# heater_control.net
KiCad netlist of a schematic drawn in Altium Designer
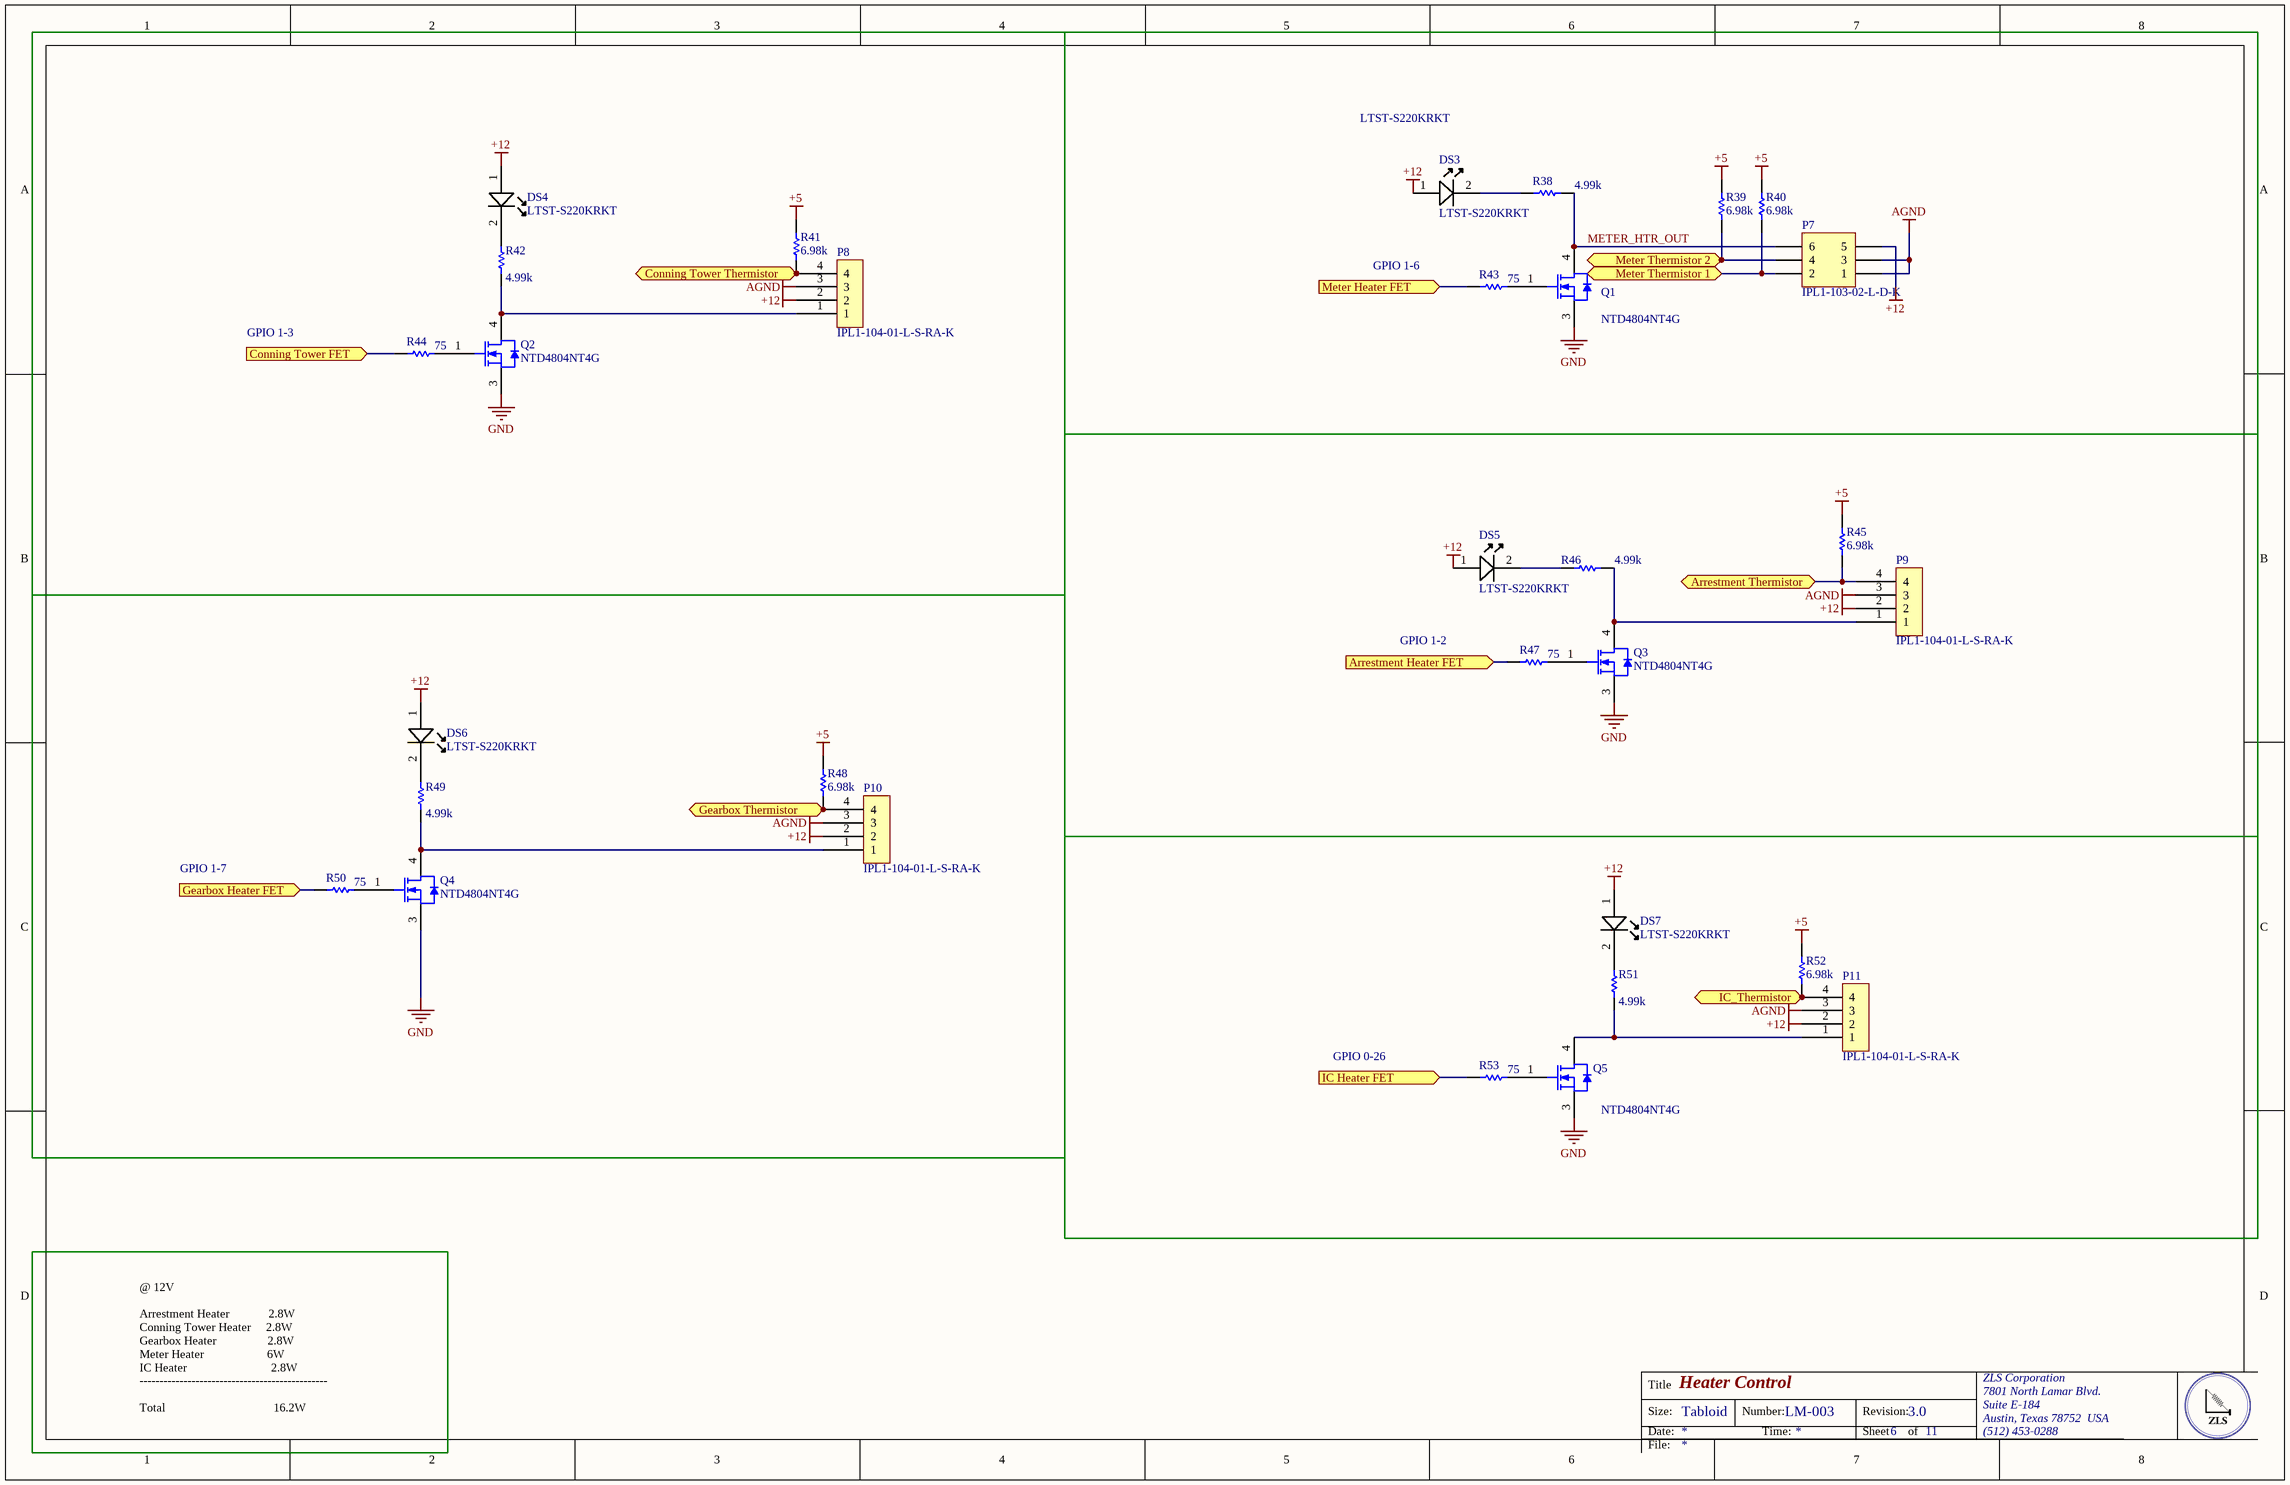
[diagram p0: heater_control.SchDoc]

(export (version "E")
  (design (tool "Eeschema 10.0.6"))
  (components
    (comp (ref "DS3")
      (value "Visible Name Value Type    False Description Lite-On LTST-S220KRKT Red LED, 631 nm 2012 (0805) Side View, Rectangle Lens SMD package STRING")
      (footprint "0805C_L")
      (fields
        (field (name "MANUFACTURER") "Vishay / Lite-On")
        (field (name "MANUFACTURER PART NUMBER") "LTST-S220KRKT")
      )
      (libsource (lib "*") (part "LED A/K"))
    )
    (comp (ref "DS4")
      (value "Visible Name Value Type    False Description Lite-On LTST-S220KRKT Red LED, 631 nm 2012 (0805) Side View, Rectangle Lens SMD package STRING")
      (footprint "0805C_L")
      (fields
        (field (name "MANUFACTURER") "Vishay / Lite-On")
        (field (name "MANUFACTURER PART NUMBER") "LTST-S220KRKT")
      )
      (libsource (lib "*") (part "LED A/K"))
    )
    (comp (ref "DS5")
      (value "Visible Name Value Type    False Description Lite-On LTST-S220KRKT Red LED, 631 nm 2012 (0805) Side View, Rectangle Lens SMD package STRING")
      (footprint "0805C_L")
      (fields
        (field (name "MANUFACTURER") "Vishay / Lite-On")
        (field (name "MANUFACTURER PART NUMBER") "LTST-S220KRKT")
      )
      (libsource (lib "*") (part "LED A/K"))
    )
    (comp (ref "DS6")
      (value "Visible Name Value Type    False Description Lite-On LTST-S220KRKT Red LED, 631 nm 2012 (0805) Side View, Rectangle Lens SMD package STRING")
      (footprint "0805C_L")
      (fields
        (field (name "MANUFACTURER") "Vishay / Lite-On")
        (field (name "MANUFACTURER PART NUMBER") "LTST-S220KRKT")
      )
      (libsource (lib "*") (part "LED A/K"))
    )
    (comp (ref "DS7")
      (value "Visible Name Value Type    False Description Lite-On LTST-S220KRKT Red LED, 631 nm 2012 (0805) Side View, Rectangle Lens SMD package STRING")
      (footprint "0805C_L")
      (fields
        (field (name "MANUFACTURER") "Vishay / Lite-On")
        (field (name "MANUFACTURER PART NUMBER") "LTST-S220KRKT")
      )
      (libsource (lib "*") (part "LED A/K"))
    )
    (comp (ref "P7")
      (value "IPL1-103-02-L-D-K")
      (footprint "IPL1-103-01-D")
      (description "CONN SHROUDED PWR HEADER 3POS")
      (libsource (lib "Miscellaneous Connectors") (part "Header 3X2H"))
    )
    (comp (ref "P8")
      (value "IPL1-104-01-L-S-RA-K")
      (footprint "IPL1-104-01")
      (description ".100 TERMINAL ASSY")
      (libsource (lib "ZLS_LIB") (part "53047-0410"))
    )
    (comp (ref "P9")
      (value "IPL1-104-01-L-S-RA-K")
      (footprint "IPL1-104-01")
      (description ".100 TERMINAL ASSY")
      (libsource (lib "ZLS_LIB") (part "53047-0410"))
    )
    (comp (ref "P10")
      (value "IPL1-104-01-L-S-RA-K")
      (footprint "IPL1-104-01")
      (description ".100 TERMINAL ASSY")
      (libsource (lib "ZLS_LIB") (part "53047-0410"))
    )
    (comp (ref "P11")
      (value "IPL1-104-01-L-S-RA-K")
      (footprint "IPL1-104-01")
      (description ".100 TERMINAL ASSY")
      (libsource (lib "ZLS_LIB") (part "53047-0410"))
    )
    (comp (ref "Q1")
      (value "NTD4804NT4G")
      (footprint "ONSC-DPAK-3-369AA-01_V")
      (description "Power MOSFET, 30 V, 117 A, Single N-Channel, 3-Pin DPAK, Pb-Free, Tape and Reel")
      (fields (field (name "MANUFACTURER") "On Semiconductor"))
      (libsource (lib "Altium Content Vault") (part "CMP-1058-00341-1"))
    )
    (comp (ref "Q2")
      (value "NTD4804NT4G")
      (footprint "ONSC-DPAK-3-369AA-01_V")
      (description "Power MOSFET, 30 V, 117 A, Single N-Channel, 3-Pin DPAK, Pb-Free, Tape and Reel")
      (fields (field (name "MANUFACTURER") "On Semiconductor"))
      (libsource (lib "Altium Content Vault") (part "CMP-1058-00341-1"))
    )
    (comp (ref "Q3")
      (value "NTD4804NT4G")
      (footprint "ONSC-DPAK-3-369AA-01_V")
      (description "Power MOSFET, 30 V, 117 A, Single N-Channel, 3-Pin DPAK, Pb-Free, Tape and Reel")
      (fields (field (name "MANUFACTURER") "On Semiconductor"))
      (libsource (lib "Altium Content Vault") (part "CMP-1058-00341-1"))
    )
    (comp (ref "Q4")
      (value "NTD4804NT4G")
      (footprint "ONSC-DPAK-3-369AA-01_V")
      (description "Power MOSFET, 30 V, 117 A, Single N-Channel, 3-Pin DPAK, Pb-Free, Tape and Reel")
      (fields (field (name "MANUFACTURER") "On Semiconductor"))
      (libsource (lib "Altium Content Vault") (part "CMP-1058-00341-1"))
    )
    (comp (ref "Q5")
      (value "NTD4804NT4G")
      (footprint "ONSC-DPAK-3-369AA-01_V")
      (description "Power MOSFET, 30 V, 117 A, Single N-Channel, 3-Pin DPAK, Pb-Free, Tape and Reel")
      (fields (field (name "MANUFACTURER") "On Semiconductor"))
      (libsource (lib "Altium Content Vault") (part "CMP-1058-00341-1"))
    )
    (comp (ref "R38")
      (value "~")
      (footprint "RESC0805(2012)_L")
      (fields
        (field (name "MANUFACTURER") "Vishay Dale")
        (field (name "MANUFACTURER PART NUMBER") "CRCW08054K99FKEA")
        (field (name "RESISTANCE (OHMS)") "4.99k")
        (field (name "TOLERANCE") "±1%")
      )
      (libsource (lib "Altium Content Vault") (part "CMP-1013-00393-1"))
    )
    (comp (ref "R39")
      (value "6K98 1% 0805(2012)")
      (footprint "RESC0805(2012)_N")
      (description "6K98 0.125W 1% 0805 (2012 Metric)  SMD")
      (fields
        (field (name "MANUFACTURER") "Vishay Dale")
        (field (name "MANUFACTURER PART NUMBER") "CRCW08056K98FKEA")
        (field (name "RESISTANCE (OHMS)") "6.98k")
      )
      (libsource (lib "Altium Content Vault") (part "CMP-1013-00606-1"))
    )
    (comp (ref "R40")
      (value "6K98 1% 0805(2012)")
      (footprint "RESC0805(2012)_N")
      (description "6K98 0.125W 1% 0805 (2012 Metric)  SMD")
      (fields
        (field (name "MANUFACTURER") "Vishay Dale")
        (field (name "MANUFACTURER PART NUMBER") "CRCW08056K98FKEA")
        (field (name "RESISTANCE (OHMS)") "6.98k")
      )
      (libsource (lib "Altium Content Vault") (part "CMP-1013-00606-1"))
    )
    (comp (ref "R41")
      (value "6K98 1% 0805(2012)")
      (footprint "RESC0805(2012)_N")
      (description "6K98 0.125W 1% 0805 (2012 Metric)  SMD")
      (fields
        (field (name "MANUFACTURER") "Vishay Dale")
        (field (name "MANUFACTURER PART NUMBER") "CRCW08056K98FKEA")
        (field (name "RESISTANCE (OHMS)") "6.98k")
      )
      (libsource (lib "Altium Content Vault") (part "CMP-1013-00606-1"))
    )
    (comp (ref "R42")
      (value "~")
      (footprint "RESC0805(2012)_L")
      (fields
        (field (name "MANUFACTURER") "Vishay Dale")
        (field (name "MANUFACTURER PART NUMBER") "CRCW08054K99FKEA")
        (field (name "RESISTANCE (OHMS)") "4.99k")
        (field (name "TOLERANCE") "±1%")
      )
      (libsource (lib "Altium Content Vault") (part "CMP-1013-00393-1"))
    )
    (comp (ref "R43")
      (value "~")
      (footprint "RESC0805(2012)_L")
      (fields
        (field (name "MANUFACTURER") "Vishay Dale")
        (field (name "MANUFACTURER PART NUMBER") "CRCW080575R0FKEA")
        (field (name "RESISTANCE (OHMS)") "75")
        (field (name "TOLERANCE") "±1%")
      )
      (libsource (lib "Altium Content Vault") (part "CMP-1013-00393-1"))
    )
    (comp (ref "R44")
      (value "~")
      (footprint "RESC0805(2012)_L")
      (fields
        (field (name "MANUFACTURER") "Vishay Dale")
        (field (name "MANUFACTURER PART NUMBER") "CRCW080575R0FKEA")
        (field (name "RESISTANCE (OHMS)") "75")
        (field (name "TOLERANCE") "±1%")
      )
      (libsource (lib "Altium Content Vault") (part "CMP-1013-00393-1"))
    )
    (comp (ref "R45")
      (value "6K98 1% 0805(2012)")
      (footprint "RESC0805(2012)_N")
      (description "6K98 0.125W 1% 0805 (2012 Metric)  SMD")
      (fields
        (field (name "MANUFACTURER") "Vishay Dale")
        (field (name "MANUFACTURER PART NUMBER") "CRCW08056K98FKEA")
        (field (name "RESISTANCE (OHMS)") "6.98k")
      )
      (libsource (lib "Altium Content Vault") (part "CMP-1013-00606-1"))
    )
    (comp (ref "R46")
      (value "~")
      (footprint "RESC0805(2012)_L")
      (fields
        (field (name "MANUFACTURER") "Vishay Dale")
        (field (name "MANUFACTURER PART NUMBER") "CRCW08054K99FKEA")
        (field (name "RESISTANCE (OHMS)") "4.99k")
        (field (name "TOLERANCE") "±1%")
      )
      (libsource (lib "Altium Content Vault") (part "CMP-1013-00393-1"))
    )
    (comp (ref "R47")
      (value "~")
      (footprint "RESC0805(2012)_L")
      (fields
        (field (name "MANUFACTURER") "Vishay Dale")
        (field (name "MANUFACTURER PART NUMBER") "CRCW080575R0FKEA")
        (field (name "RESISTANCE (OHMS)") "75")
        (field (name "TOLERANCE") "±1%")
      )
      (libsource (lib "Altium Content Vault") (part "CMP-1013-00393-1"))
    )
    (comp (ref "R48")
      (value "6K98 1% 0805(2012)")
      (footprint "RESC0805(2012)_N")
      (description "6K98 0.125W 1% 0805 (2012 Metric)  SMD")
      (fields
        (field (name "MANUFACTURER") "Vishay Dale")
        (field (name "MANUFACTURER PART NUMBER") "CRCW08056K98FKEA")
        (field (name "RESISTANCE (OHMS)") "6.98k")
      )
      (libsource (lib "Altium Content Vault") (part "CMP-1013-00606-1"))
    )
    (comp (ref "R49")
      (value "~")
      (footprint "RESC0805(2012)_L")
      (fields
        (field (name "MANUFACTURER") "Vishay Dale")
        (field (name "MANUFACTURER PART NUMBER") "CRCW08054K99FKEA")
        (field (name "RESISTANCE (OHMS)") "4.99k")
        (field (name "TOLERANCE") "±1%")
      )
      (libsource (lib "Altium Content Vault") (part "CMP-1013-00393-1"))
    )
    (comp (ref "R50")
      (value "~")
      (footprint "RESC0805(2012)_L")
      (fields
        (field (name "MANUFACTURER") "Vishay Dale")
        (field (name "MANUFACTURER PART NUMBER") "CRCW080575R0FKEA")
        (field (name "RESISTANCE (OHMS)") "75")
        (field (name "TOLERANCE") "±1%")
      )
      (libsource (lib "Altium Content Vault") (part "CMP-1013-00393-1"))
    )
    (comp (ref "R51")
      (value "~")
      (footprint "RESC0805(2012)_L")
      (fields
        (field (name "MANUFACTURER") "Vishay Dale")
        (field (name "MANUFACTURER PART NUMBER") "CRCW08054K99FKEA")
        (field (name "RESISTANCE (OHMS)") "4.99k")
        (field (name "TOLERANCE") "±1%")
      )
      (libsource (lib "Altium Content Vault") (part "CMP-1013-00393-1"))
    )
    (comp (ref "R52")
      (value "6K98 1% 0805(2012)")
      (footprint "RESC0805(2012)_N")
      (description "6K98 0.125W 1% 0805 (2012 Metric)  SMD")
      (fields
        (field (name "MANUFACTURER") "Vishay Dale")
        (field (name "MANUFACTURER PART NUMBER") "CRCW08056K98FKEA")
        (field (name "RESISTANCE (OHMS)") "6.98k")
      )
      (libsource (lib "Altium Content Vault") (part "CMP-1013-00606-1"))
    )
    (comp (ref "R53")
      (value "~")
      (footprint "RESC0805(2012)_L")
      (fields
        (field (name "MANUFACTURER") "Vishay Dale")
        (field (name "MANUFACTURER PART NUMBER") "CRCW080575R0FKEA")
        (field (name "RESISTANCE (OHMS)") "75")
        (field (name "TOLERANCE") "±1%")
      )
      (libsource (lib "Altium Content Vault") (part "CMP-1013-00393-1"))
    )
  )
  (nets
    (net (code "1") (name "+5") (class "Default")
      (node (ref "R39") (pin "1") (pinfunction "1_1") (pintype "passive"))
      (node (ref "R40") (pin "2") (pinfunction "2_2") (pintype "passive"))
      (node (ref "R41") (pin "2") (pinfunction "2_2") (pintype "passive"))
      (node (ref "R45") (pin "1") (pinfunction "1_1") (pintype "passive"))
      (node (ref "R48") (pin "2") (pinfunction "2_2") (pintype "passive"))
      (node (ref "R52") (pin "1") (pinfunction "1_1") (pintype "passive"))
    )
    (net (code "2") (name "+12") (class "Default")
      (node (ref "DS3") (pin "1") (pinfunction "A_1") (pintype "passive"))
      (node (ref "DS4") (pin "1") (pinfunction "A_1") (pintype "passive"))
      (node (ref "DS5") (pin "1") (pinfunction "A_1") (pintype "passive"))
      (node (ref "DS6") (pin "1") (pinfunction "A_1") (pintype "passive"))
      (node (ref "DS7") (pin "1") (pinfunction "A_1") (pintype "passive"))
      (node (ref "P10") (pin "2") (pinfunction "2_2") (pintype "passive"))
      (node (ref "P11") (pin "2") (pinfunction "2_2") (pintype "passive"))
      (node (ref "P7") (pin "5") (pinfunction "5_5") (pintype "passive"))
      (node (ref "P8") (pin "2") (pinfunction "2_2") (pintype "passive"))
      (node (ref "P9") (pin "2") (pinfunction "2_2") (pintype "passive"))
    )
    (net (code "3") (name "/Arrestment Heater FET") (class "Default")
      (node (ref "R47") (pin "1") (pinfunction "1_1") (pintype "passive"))
    )
    (net (code "4") (name "/Arrestment Thermistor") (class "Default")
      (node (ref "P9") (pin "4") (pinfunction "4_4") (pintype "passive"))
      (node (ref "R45") (pin "2") (pinfunction "2_2") (pintype "passive"))
    )
    (net (code "5") (name "/Conning Tower FET") (class "Default")
      (node (ref "R44") (pin "1") (pinfunction "1_1") (pintype "passive"))
    )
    (net (code "6") (name "/Conning Tower Thermistor") (class "Default")
      (node (ref "P8") (pin "4") (pinfunction "4_4") (pintype "passive"))
      (node (ref "R41") (pin "1") (pinfunction "1_1") (pintype "passive"))
    )
    (net (code "7") (name "/Gearbox Heater FET") (class "Default")
      (node (ref "R50") (pin "1") (pinfunction "1_1") (pintype "passive"))
    )
    (net (code "8") (name "/Gearbox Thermistor") (class "Default")
      (node (ref "P10") (pin "4") (pinfunction "4_4") (pintype "passive"))
      (node (ref "R48") (pin "1") (pinfunction "1_1") (pintype "passive"))
    )
    (net (code "9") (name "/IC Heater FET") (class "Default")
      (node (ref "R53") (pin "1") (pinfunction "1_1") (pintype "passive"))
    )
    (net (code "10") (name "/IC_Thermistor") (class "Default")
      (node (ref "P11") (pin "4") (pinfunction "4_4") (pintype "passive"))
      (node (ref "R52") (pin "2") (pinfunction "2_2") (pintype "passive"))
    )
    (net (code "11") (name "/METER_HTR_OUT") (class "Default")
      (node (ref "P7") (pin "6") (pinfunction "6_6") (pintype "passive"))
      (node (ref "Q1") (pin "4") (pinfunction "D_4") (pintype "passive"))
      (node (ref "R38") (pin "2") (pinfunction "2_2") (pintype "passive"))
    )
    (net (code "12") (name "/Meter Heater FET") (class "Default")
      (node (ref "R43") (pin "1") (pinfunction "1_1") (pintype "passive"))
    )
    (net (code "13") (name "/Meter Thermistor 1") (class "Default")
      (node (ref "P7") (pin "2") (pinfunction "2_2") (pintype "passive"))
      (node (ref "R40") (pin "1") (pinfunction "1_1") (pintype "passive"))
    )
    (net (code "14") (name "/Meter Thermistor 2") (class "Default")
      (node (ref "P7") (pin "4") (pinfunction "4_4") (pintype "passive"))
      (node (ref "R39") (pin "2") (pinfunction "2_2") (pintype "passive"))
    )
    (net (code "15") (name "AGND") (class "Default")
      (node (ref "P10") (pin "3") (pinfunction "3_3") (pintype "passive"))
      (node (ref "P11") (pin "3") (pinfunction "3_3") (pintype "passive"))
      (node (ref "P7") (pin "1") (pinfunction "1_1") (pintype "passive"))
      (node (ref "P7") (pin "3") (pinfunction "3_3") (pintype "passive"))
      (node (ref "P8") (pin "3") (pinfunction "3_3") (pintype "passive"))
      (node (ref "P9") (pin "3") (pinfunction "3_3") (pintype "passive"))
    )
    (net (code "16") (name "GND") (class "Default")
      (node (ref "Q1") (pin "3") (pinfunction "S_3") (pintype "passive"))
      (node (ref "Q2") (pin "3") (pinfunction "S_3") (pintype "passive"))
      (node (ref "Q3") (pin "3") (pinfunction "S_3") (pintype "passive"))
      (node (ref "Q4") (pin "3") (pinfunction "S_3") (pintype "passive"))
      (node (ref "Q5") (pin "3") (pinfunction "S_3") (pintype "passive"))
    )
    (net (code "17") (name "Net-(DS3-K)") (class "Default")
      (node (ref "DS3") (pin "2") (pinfunction "K_2") (pintype "passive"))
      (node (ref "R38") (pin "1") (pinfunction "1_1") (pintype "passive"))
    )
    (net (code "18") (name "Net-(DS4-K)") (class "Default")
      (node (ref "DS4") (pin "2") (pinfunction "K_2") (pintype "passive"))
      (node (ref "R42") (pin "2") (pinfunction "2_2") (pintype "passive"))
    )
    (net (code "19") (name "Net-(DS5-K)") (class "Default")
      (node (ref "DS5") (pin "2") (pinfunction "K_2") (pintype "passive"))
      (node (ref "R46") (pin "1") (pinfunction "1_1") (pintype "passive"))
    )
    (net (code "20") (name "Net-(DS6-K)") (class "Default")
      (node (ref "DS6") (pin "2") (pinfunction "K_2") (pintype "passive"))
      (node (ref "R49") (pin "2") (pinfunction "2_2") (pintype "passive"))
    )
    (net (code "21") (name "Net-(DS7-K)") (class "Default")
      (node (ref "DS7") (pin "2") (pinfunction "K_2") (pintype "passive"))
      (node (ref "R51") (pin "1") (pinfunction "1_1") (pintype "passive"))
    )
    (net (code "22") (name "Net-(Q1-G)") (class "Default")
      (node (ref "Q1") (pin "1") (pinfunction "G_1") (pintype "passive"))
      (node (ref "R43") (pin "2") (pinfunction "2_2") (pintype "passive"))
    )
    (net (code "23") (name "Net-(Q2-D)") (class "Default")
      (node (ref "P8") (pin "1") (pinfunction "1_1") (pintype "passive"))
      (node (ref "Q2") (pin "4") (pinfunction "D_4") (pintype "passive"))
      (node (ref "R42") (pin "1") (pinfunction "1_1") (pintype "passive"))
    )
    (net (code "24") (name "Net-(Q2-G)") (class "Default")
      (node (ref "Q2") (pin "1") (pinfunction "G_1") (pintype "passive"))
      (node (ref "R44") (pin "2") (pinfunction "2_2") (pintype "passive"))
    )
    (net (code "25") (name "Net-(Q3-D)") (class "Default")
      (node (ref "P9") (pin "1") (pinfunction "1_1") (pintype "passive"))
      (node (ref "Q3") (pin "4") (pinfunction "D_4") (pintype "passive"))
      (node (ref "R46") (pin "2") (pinfunction "2_2") (pintype "passive"))
    )
    (net (code "26") (name "Net-(Q3-G)") (class "Default")
      (node (ref "Q3") (pin "1") (pinfunction "G_1") (pintype "passive"))
      (node (ref "R47") (pin "2") (pinfunction "2_2") (pintype "passive"))
    )
    (net (code "27") (name "Net-(Q4-D)") (class "Default")
      (node (ref "P10") (pin "1") (pinfunction "1_1") (pintype "passive"))
      (node (ref "Q4") (pin "4") (pinfunction "D_4") (pintype "passive"))
      (node (ref "R49") (pin "1") (pinfunction "1_1") (pintype "passive"))
    )
    (net (code "28") (name "Net-(Q4-G)") (class "Default")
      (node (ref "Q4") (pin "1") (pinfunction "G_1") (pintype "passive"))
      (node (ref "R50") (pin "2") (pinfunction "2_2") (pintype "passive"))
    )
    (net (code "29") (name "Net-(Q5-D)") (class "Default")
      (node (ref "P11") (pin "1") (pinfunction "1_1") (pintype "passive"))
      (node (ref "Q5") (pin "4") (pinfunction "D_4") (pintype "passive"))
      (node (ref "R51") (pin "2") (pinfunction "2_2") (pintype "passive"))
    )
    (net (code "30") (name "Net-(Q5-G)") (class "Default")
      (node (ref "Q5") (pin "1") (pinfunction "G_1") (pintype "passive"))
      (node (ref "R53") (pin "2") (pinfunction "2_2") (pintype "passive"))
    )
  )
)
